# Sheet1.net
KiCad netlist of a schematic drawn in Altium Designer
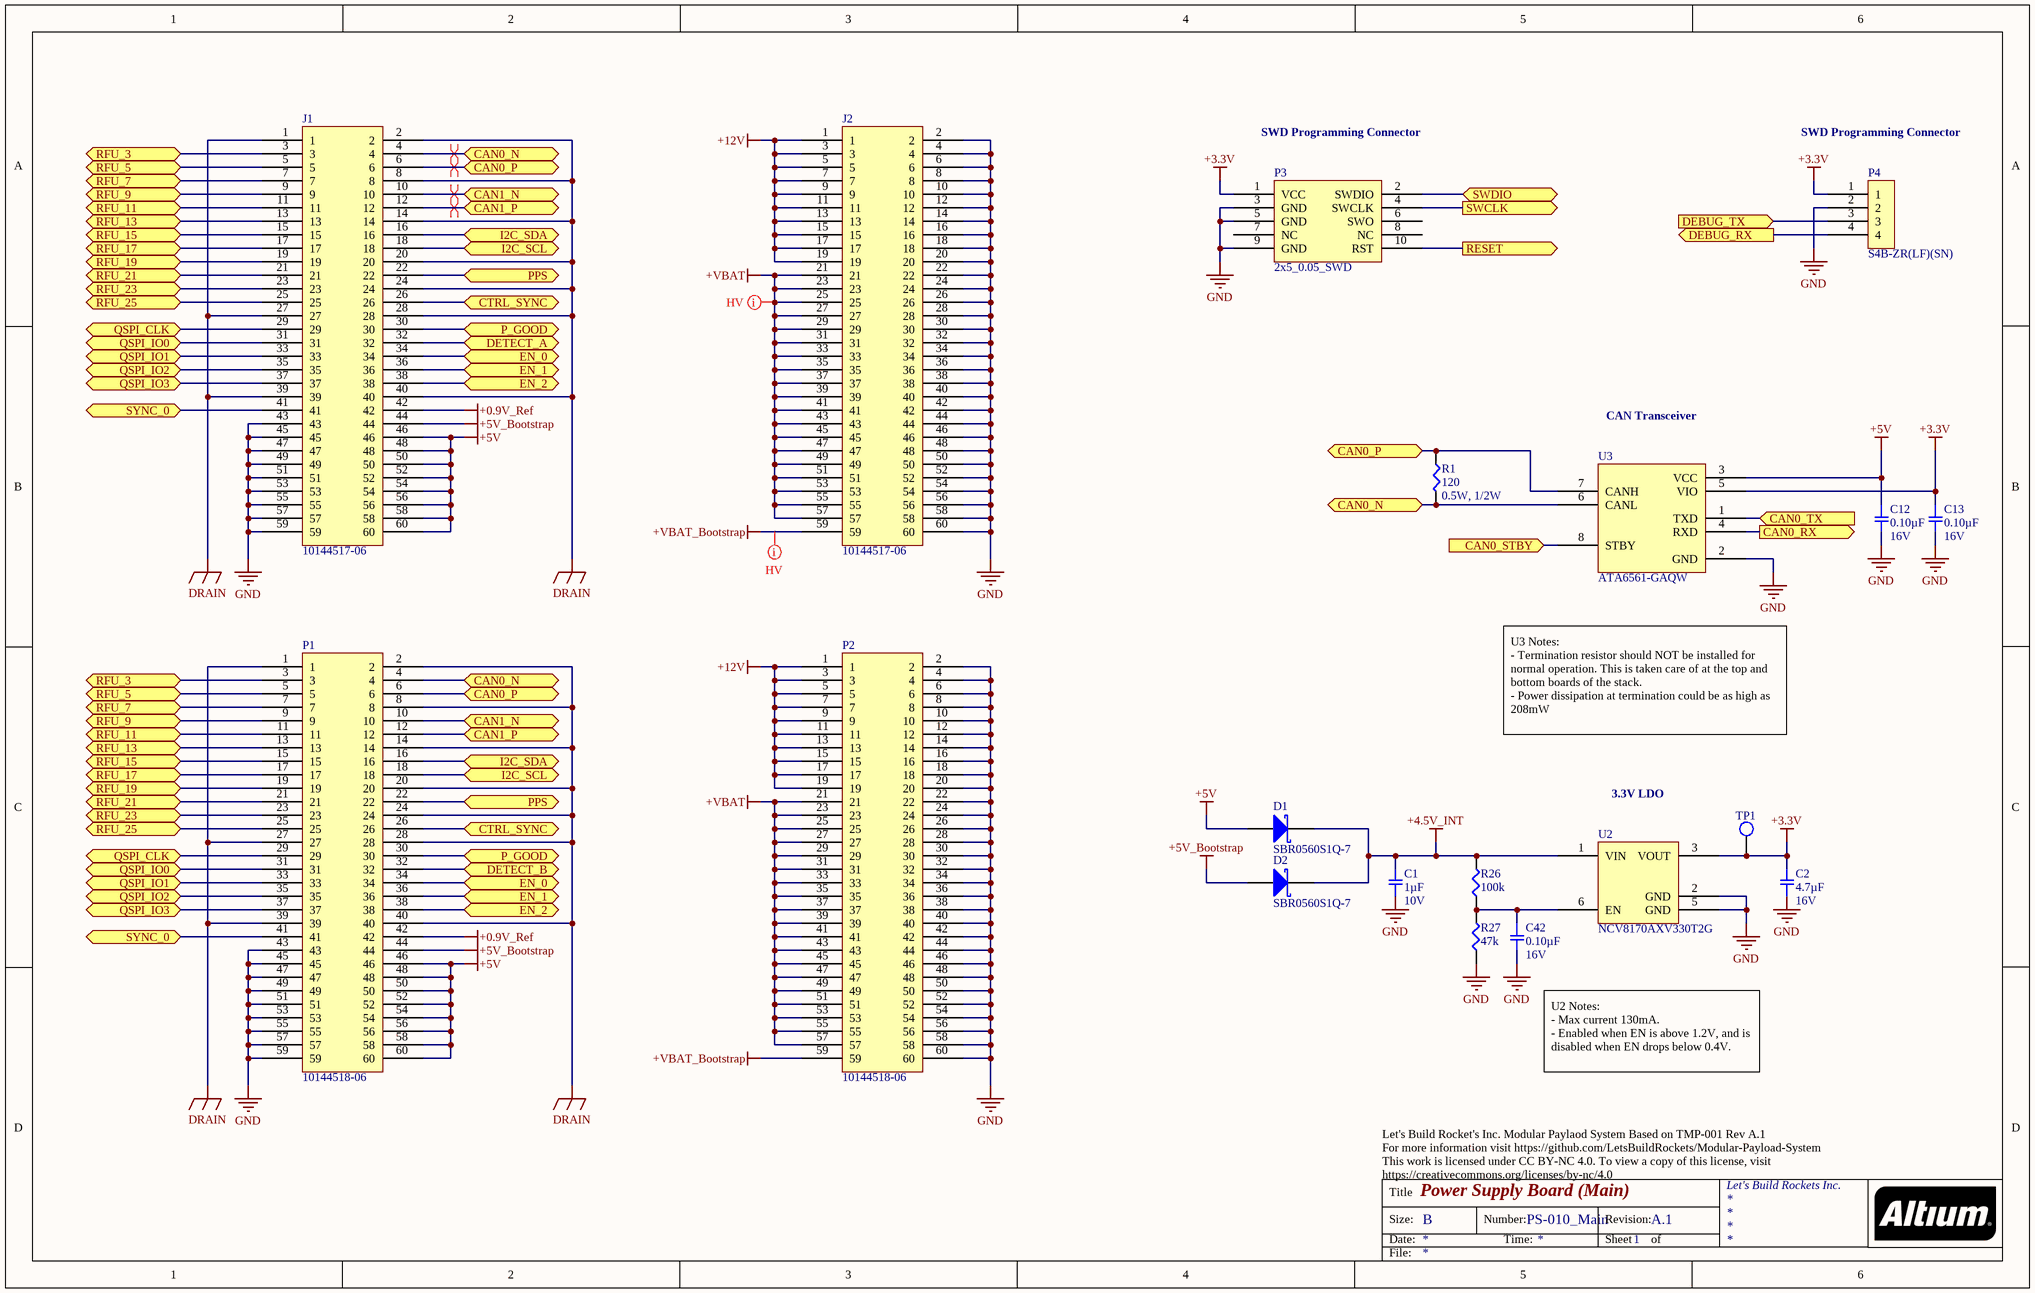
[diagram p0: Sheet1.SchDoc]

(export (version "E")
  (design (tool "Eeschema 10.0.6"))
  (components
    (comp (ref "C1")
      (value "1µF")
      (footprint "SMD-0402C")
      (description "CAP CER 1UF 10V X7S 0402")
      (fields
        (field (name "DIGI-KEY PART NUMBER") "490-13409-1-ND")
        (field (name "PART NUMBER") "GCM155C71A105KE38D")
        (field (name "VOLTAGE") "10V")
      )
      (libsource (lib "capacitor_murata_0402") (part "GCM155C71A105KE38D"))
    )
    (comp (ref "C2")
      (value "4.7µF")
      (footprint "SMD-0805C")
      (description "CAP CER 4.7UF 16V X7R 0805")
      (fields
        (field (name "DIGI-KEY PART NUMBER") "490-10557-1-ND")
        (field (name "PART NUMBER") "GCJ21BR71C475KA01L")
        (field (name "VOLTAGE") "16V")
      )
      (libsource (lib "capacitor_murata_0805") (part "GCJ21BR71C475KA01L"))
    )
    (comp (ref "C12")
      (value "0.10µF")
      (footprint "SMD-0402C")
      (description "CAP CER 0.1UF 16V X7R 0402")
      (fields
        (field (name "DIGI-KEY PART NUMBER") "490-4759-1-ND")
        (field (name "PART NUMBER") "GCM155R71C104KA55D")
        (field (name "VOLTAGE") "16V")
      )
      (libsource (lib "capacitor_murata_0402") (part "GCM155R71C104KA55D"))
    )
    (comp (ref "C13")
      (value "0.10µF")
      (footprint "SMD-0402C")
      (description "CAP CER 0.1UF 16V X7R 0402")
      (fields
        (field (name "DIGI-KEY PART NUMBER") "490-4759-1-ND")
        (field (name "PART NUMBER") "GCM155R71C104KA55D")
        (field (name "VOLTAGE") "16V")
      )
      (libsource (lib "capacitor_murata_0402") (part "GCM155R71C104KA55D"))
    )
    (comp (ref "C42")
      (value "0.10µF")
      (footprint "SMD-0402C")
      (description "CAP CER 0.1UF 16V X7R 0402")
      (fields
        (field (name "DIGI-KEY PART NUMBER") "490-4759-1-ND")
        (field (name "PART NUMBER") "GCM155R71C104KA55D")
        (field (name "VOLTAGE") "16V")
      )
      (libsource (lib "capacitor_murata_0402") (part "GCM155R71C104KA55D"))
    )
    (comp (ref "D1")
      (value "SBR0560S1Q-7")
      (footprint "SOD123")
      (libsource (lib "ModularPayload") (part "SBR0560S1Q-7"))
    )
    (comp (ref "D2")
      (value "SBR0560S1Q-7")
      (footprint "SOD123")
      (libsource (lib "ModularPayload") (part "SBR0560S1Q-7"))
    )
    (comp (ref "J1")
      (value "10144517-06")
      (footprint "10144517-062802LF")
      (libsource (lib "ModularPayload") (part "10144517-06"))
    )
    (comp (ref "J2")
      (value "10144517-06")
      (footprint "10144517-062802LF")
      (libsource (lib "ModularPayload") (part "10144517-06"))
    )
    (comp (ref "P1")
      (value "10144518-06")
      (footprint "10144518-064802LF")
      (libsource (lib "ModularPayload") (part "10144518-06"))
    )
    (comp (ref "P2")
      (value "10144518-06")
      (footprint "10144518-064802LF")
      (libsource (lib "ModularPayload") (part "10144518-06"))
    )
    (comp (ref "P3")
      (value "2x5_0.05_SWD")
      (footprint "2x5_0.05_R")
      (libsource (lib "ModularPayload") (part "2x5_0.05_SWD"))
    )
    (comp (ref "P4")
      (value "S4B-ZR(LF)(SN)")
      (footprint "S4B-ZR(LF)(SN)")
      (libsource (lib "ModularPayload") (part "S4B-ZR(LF)(SN)"))
    )
    (comp (ref "R1")
      (value "120")
      (footprint "SMD-0805-RES")
      (description "RES SMD 120 OHM 5% 1/2W 0805")
      (fields
        (field (name "PART NUMBER") "ERJ-P6WJ121V")
        (field (name "DIGI-KEY PART NUMBER") "P16943CT-ND")
        (field (name "POWER (WATTS)") "0.5W, 1/2W")
      )
      (libsource (lib "Panasonic_ERJ_0805") (part "ERJ-P6WJ121V"))
    )
    (comp (ref "R26")
      (value "100k")
      (footprint "SMD-0402-RES")
      (description "RES SMD 100K OHM 5% 1/10W 0402")
      (fields (field (name "PART NUMBER") "ERJ-2GEJ104X") (field (name "DIGI-KEY PART NUMBER") "P100KJCT-ND"))
      (libsource (lib "Panasonic_ERJ_0402") (part "ERJ-2GEJ104X"))
    )
    (comp (ref "R27")
      (value "47k")
      (footprint "SMD-0402-RES")
      (description "RES SMD 47K OHM 5% 1/10W 0402")
      (fields (field (name "PART NUMBER") "ERJ-2GEJ473X") (field (name "DIGI-KEY PART NUMBER") "P47KJCT-ND"))
      (libsource (lib "Panasonic_ERJ_0402") (part "ERJ-2GEJ473X"))
    )
    (comp (ref "TP1") (value "TP") (footprint "TP_SMD_40") (libsource (lib "TP") (part "TP")))
    (comp (ref "U2")
      (value "NCV8170AXV330T2G")
      (footprint "SOTFL50P160X60-6N")
      (libsource (lib "ModularPayload") (part "NCV8170AXV330T2G"))
    )
    (comp (ref "U3")
      (value "ATA6561-GAQW")
      (footprint "SOIC127P600X175-8N")
      (libsource (lib "ModularPayload") (part "ATA6561-GAQW"))
    )
  )
  (nets
    (net (code "1") (name "+0.9V_Ref") (class "Default")
      (node (ref "J1") (pin "42") (pinfunction "42_42") (pintype "passive"))
      (node (ref "P1") (pin "42") (pinfunction "42_42") (pintype "passive"))
    )
    (net (code "2") (name "+3.3V") (class "Default")
      (node (ref "C13") (pin "1") (pinfunction "1_1") (pintype "passive"))
      (node (ref "C2") (pin "2") (pinfunction "2_2") (pintype "passive"))
      (node (ref "P3") (pin "1") (pinfunction "VCC_1") (pintype "passive"))
      (node (ref "P4") (pin "1") (pinfunction "1_1") (pintype "passive"))
      (node (ref "TP1") (pin "1") (pintype "passive"))
      (node (ref "U2") (pin "3") (pinfunction "VOUT_3") (pintype "passive"))
      (node (ref "U3") (pin "5") (pinfunction "VIO_5") (pintype "passive"))
    )
    (net (code "3") (name "+4.5V_INT") (class "Default")
      (node (ref "C1") (pin "2") (pinfunction "2_2") (pintype "passive"))
      (node (ref "D1") (pin "K") (pinfunction "K_K") (pintype "passive"))
      (node (ref "D2") (pin "K") (pinfunction "K_K") (pintype "passive"))
      (node (ref "R26") (pin "2") (pinfunction "2_2") (pintype "passive"))
      (node (ref "U2") (pin "1") (pinfunction "VIN_1") (pintype "passive"))
    )
    (net (code "4") (name "+5V") (class "Default")
      (node (ref "C12") (pin "1") (pinfunction "1_1") (pintype "passive"))
      (node (ref "D1") (pin "A") (pinfunction "A_A") (pintype "passive"))
      (node (ref "J1") (pin "46") (pinfunction "46_46") (pintype "passive"))
      (node (ref "J1") (pin "48") (pinfunction "48_48") (pintype "passive"))
      (node (ref "J1") (pin "50") (pinfunction "50_50") (pintype "passive"))
      (node (ref "J1") (pin "52") (pinfunction "52_52") (pintype "passive"))
      (node (ref "J1") (pin "54") (pinfunction "54_54") (pintype "passive"))
      (node (ref "J1") (pin "56") (pinfunction "56_56") (pintype "passive"))
      (node (ref "J1") (pin "58") (pinfunction "58_58") (pintype "passive"))
      (node (ref "J1") (pin "60") (pinfunction "60_60") (pintype "passive"))
      (node (ref "P1") (pin "46") (pinfunction "46_46") (pintype "passive"))
      (node (ref "P1") (pin "48") (pinfunction "48_48") (pintype "passive"))
      (node (ref "P1") (pin "50") (pinfunction "50_50") (pintype "passive"))
      (node (ref "P1") (pin "52") (pinfunction "52_52") (pintype "passive"))
      (node (ref "P1") (pin "54") (pinfunction "54_54") (pintype "passive"))
      (node (ref "P1") (pin "56") (pinfunction "56_56") (pintype "passive"))
      (node (ref "P1") (pin "58") (pinfunction "58_58") (pintype "passive"))
      (node (ref "P1") (pin "60") (pinfunction "60_60") (pintype "passive"))
      (node (ref "U3") (pin "3") (pinfunction "VCC_3") (pintype "passive"))
    )
    (net (code "5") (name "+5V_Bootstrap") (class "Default")
      (node (ref "D2") (pin "A") (pinfunction "A_A") (pintype "passive"))
      (node (ref "J1") (pin "44") (pinfunction "44_44") (pintype "passive"))
      (node (ref "P1") (pin "44") (pinfunction "44_44") (pintype "passive"))
    )
    (net (code "6") (name "+12V") (class "Default")
      (node (ref "J2") (pin "1") (pinfunction "1_1") (pintype "passive"))
      (node (ref "J2") (pin "11") (pinfunction "11_11") (pintype "passive"))
      (node (ref "J2") (pin "13") (pinfunction "13_13") (pintype "passive"))
      (node (ref "J2") (pin "15") (pinfunction "15_15") (pintype "passive"))
      (node (ref "J2") (pin "17") (pinfunction "17_17") (pintype "passive"))
      (node (ref "J2") (pin "19") (pinfunction "19_19") (pintype "passive"))
      (node (ref "J2") (pin "3") (pinfunction "3_3") (pintype "passive"))
      (node (ref "J2") (pin "5") (pinfunction "5_5") (pintype "passive"))
      (node (ref "J2") (pin "7") (pinfunction "7_7") (pintype "passive"))
      (node (ref "J2") (pin "9") (pinfunction "9_9") (pintype "passive"))
      (node (ref "P2") (pin "1") (pinfunction "1_1") (pintype "passive"))
      (node (ref "P2") (pin "11") (pinfunction "11_11") (pintype "passive"))
      (node (ref "P2") (pin "13") (pinfunction "13_13") (pintype "passive"))
      (node (ref "P2") (pin "15") (pinfunction "15_15") (pintype "passive"))
      (node (ref "P2") (pin "17") (pinfunction "17_17") (pintype "passive"))
      (node (ref "P2") (pin "19") (pinfunction "19_19") (pintype "passive"))
      (node (ref "P2") (pin "3") (pinfunction "3_3") (pintype "passive"))
      (node (ref "P2") (pin "5") (pinfunction "5_5") (pintype "passive"))
      (node (ref "P2") (pin "7") (pinfunction "7_7") (pintype "passive"))
      (node (ref "P2") (pin "9") (pinfunction "9_9") (pintype "passive"))
    )
    (net (code "7") (name "+VBAT") (class "Default")
      (node (ref "J2") (pin "21") (pinfunction "21_21") (pintype "passive"))
      (node (ref "J2") (pin "23") (pinfunction "23_23") (pintype "passive"))
      (node (ref "J2") (pin "25") (pinfunction "25_25") (pintype "passive"))
      (node (ref "J2") (pin "27") (pinfunction "27_27") (pintype "passive"))
      (node (ref "J2") (pin "29") (pinfunction "29_29") (pintype "passive"))
      (node (ref "J2") (pin "31") (pinfunction "31_31") (pintype "passive"))
      (node (ref "J2") (pin "33") (pinfunction "33_33") (pintype "passive"))
      (node (ref "J2") (pin "35") (pinfunction "35_35") (pintype "passive"))
      (node (ref "J2") (pin "37") (pinfunction "37_37") (pintype "passive"))
      (node (ref "J2") (pin "39") (pinfunction "39_39") (pintype "passive"))
      (node (ref "J2") (pin "41") (pinfunction "41_41") (pintype "passive"))
      (node (ref "J2") (pin "43") (pinfunction "43_43") (pintype "passive"))
      (node (ref "J2") (pin "45") (pinfunction "45_45") (pintype "passive"))
      (node (ref "J2") (pin "47") (pinfunction "47_47") (pintype "passive"))
      (node (ref "J2") (pin "49") (pinfunction "49_49") (pintype "passive"))
      (node (ref "J2") (pin "51") (pinfunction "51_51") (pintype "passive"))
      (node (ref "J2") (pin "53") (pinfunction "53_53") (pintype "passive"))
      (node (ref "J2") (pin "55") (pinfunction "55_55") (pintype "passive"))
      (node (ref "J2") (pin "57") (pinfunction "57_57") (pintype "passive"))
      (node (ref "P2") (pin "21") (pinfunction "21_21") (pintype "passive"))
      (node (ref "P2") (pin "23") (pinfunction "23_23") (pintype "passive"))
      (node (ref "P2") (pin "25") (pinfunction "25_25") (pintype "passive"))
      (node (ref "P2") (pin "27") (pinfunction "27_27") (pintype "passive"))
      (node (ref "P2") (pin "29") (pinfunction "29_29") (pintype "passive"))
      (node (ref "P2") (pin "31") (pinfunction "31_31") (pintype "passive"))
      (node (ref "P2") (pin "33") (pinfunction "33_33") (pintype "passive"))
      (node (ref "P2") (pin "35") (pinfunction "35_35") (pintype "passive"))
      (node (ref "P2") (pin "37") (pinfunction "37_37") (pintype "passive"))
      (node (ref "P2") (pin "39") (pinfunction "39_39") (pintype "passive"))
      (node (ref "P2") (pin "41") (pinfunction "41_41") (pintype "passive"))
      (node (ref "P2") (pin "43") (pinfunction "43_43") (pintype "passive"))
      (node (ref "P2") (pin "45") (pinfunction "45_45") (pintype "passive"))
      (node (ref "P2") (pin "47") (pinfunction "47_47") (pintype "passive"))
      (node (ref "P2") (pin "49") (pinfunction "49_49") (pintype "passive"))
      (node (ref "P2") (pin "51") (pinfunction "51_51") (pintype "passive"))
      (node (ref "P2") (pin "53") (pinfunction "53_53") (pintype "passive"))
      (node (ref "P2") (pin "55") (pinfunction "55_55") (pintype "passive"))
      (node (ref "P2") (pin "57") (pinfunction "57_57") (pintype "passive"))
    )
    (net (code "8") (name "+VBAT_Bootstrap") (class "Default")
      (node (ref "J2") (pin "59") (pinfunction "59_59") (pintype "passive"))
      (node (ref "P2") (pin "59") (pinfunction "59_59") (pintype "passive"))
    )
    (net (code "9") (name "/CAN0_N") (class "Default")
      (node (ref "J1") (pin "4") (pinfunction "4_4") (pintype "passive"))
      (node (ref "P1") (pin "4") (pinfunction "4_4") (pintype "passive"))
      (node (ref "R1") (pin "2") (pinfunction "2_2") (pintype "passive"))
      (node (ref "U3") (pin "6") (pinfunction "CANL_6") (pintype "passive"))
    )
    (net (code "10") (name "/CAN0_P") (class "Default")
      (node (ref "J1") (pin "6") (pinfunction "6_6") (pintype "passive"))
      (node (ref "P1") (pin "6") (pinfunction "6_6") (pintype "passive"))
      (node (ref "R1") (pin "1") (pinfunction "1_1") (pintype "passive"))
      (node (ref "U3") (pin "7") (pinfunction "CANH_7") (pintype "passive"))
    )
    (net (code "11") (name "/CAN0_RX") (class "Default")
      (node (ref "U3") (pin "4") (pinfunction "RXD_4") (pintype "passive"))
    )
    (net (code "12") (name "/CAN0_STBY") (class "Default")
      (node (ref "U3") (pin "8") (pinfunction "STBY_8") (pintype "passive"))
    )
    (net (code "13") (name "/CAN0_TX") (class "Default")
      (node (ref "U3") (pin "1") (pinfunction "TXD_1") (pintype "passive"))
    )
    (net (code "14") (name "/CAN1_N") (class "Default")
      (node (ref "J1") (pin "10") (pinfunction "10_10") (pintype "passive"))
      (node (ref "P1") (pin "10") (pinfunction "10_10") (pintype "passive"))
    )
    (net (code "15") (name "/CAN1_P") (class "Default")
      (node (ref "J1") (pin "12") (pinfunction "12_12") (pintype "passive"))
      (node (ref "P1") (pin "12") (pinfunction "12_12") (pintype "passive"))
    )
    (net (code "16") (name "/CTRL_SYNC") (class "Default")
      (node (ref "J1") (pin "26") (pinfunction "26_26") (pintype "passive"))
      (node (ref "P1") (pin "26") (pinfunction "26_26") (pintype "passive"))
    )
    (net (code "17") (name "/DEBUG_RX") (class "Default")
      (node (ref "P4") (pin "4") (pinfunction "4_4") (pintype "passive"))
    )
    (net (code "18") (name "/DEBUG_TX") (class "Default")
      (node (ref "P4") (pin "3") (pinfunction "3_3") (pintype "passive"))
    )
    (net (code "19") (name "/DETECT_A") (class "Default")
      (node (ref "J1") (pin "32") (pinfunction "32_32") (pintype "passive"))
    )
    (net (code "20") (name "/DETECT_B") (class "Default")
      (node (ref "P1") (pin "32") (pinfunction "32_32") (pintype "passive"))
    )
    (net (code "21") (name "/EN_0") (class "Default")
      (node (ref "J1") (pin "34") (pinfunction "34_34") (pintype "passive"))
      (node (ref "P1") (pin "34") (pinfunction "34_34") (pintype "passive"))
    )
    (net (code "22") (name "/EN_1") (class "Default")
      (node (ref "J1") (pin "36") (pinfunction "36_36") (pintype "passive"))
      (node (ref "P1") (pin "36") (pinfunction "36_36") (pintype "passive"))
    )
    (net (code "23") (name "/EN_2") (class "Default")
      (node (ref "J1") (pin "38") (pinfunction "38_38") (pintype "passive"))
      (node (ref "P1") (pin "38") (pinfunction "38_38") (pintype "passive"))
    )
    (net (code "24") (name "/I2C_SCL") (class "Default")
      (node (ref "J1") (pin "18") (pinfunction "18_18") (pintype "passive"))
      (node (ref "P1") (pin "18") (pinfunction "18_18") (pintype "passive"))
    )
    (net (code "25") (name "/I2C_SDA") (class "Default")
      (node (ref "J1") (pin "16") (pinfunction "16_16") (pintype "passive"))
      (node (ref "P1") (pin "16") (pinfunction "16_16") (pintype "passive"))
    )
    (net (code "26") (name "/PPS") (class "Default")
      (node (ref "J1") (pin "22") (pinfunction "22_22") (pintype "passive"))
      (node (ref "P1") (pin "22") (pinfunction "22_22") (pintype "passive"))
    )
    (net (code "27") (name "/P_GOOD") (class "Default")
      (node (ref "J1") (pin "30") (pinfunction "30_30") (pintype "passive"))
      (node (ref "P1") (pin "30") (pinfunction "30_30") (pintype "passive"))
    )
    (net (code "28") (name "/QSPI_CLK") (class "Default")
      (node (ref "J1") (pin "29") (pinfunction "29_29") (pintype "passive"))
      (node (ref "P1") (pin "29") (pinfunction "29_29") (pintype "passive"))
    )
    (net (code "29") (name "/QSPI_IO0") (class "Default")
      (node (ref "J1") (pin "31") (pinfunction "31_31") (pintype "passive"))
      (node (ref "P1") (pin "31") (pinfunction "31_31") (pintype "passive"))
    )
    (net (code "30") (name "/QSPI_IO1") (class "Default")
      (node (ref "J1") (pin "33") (pinfunction "33_33") (pintype "passive"))
      (node (ref "P1") (pin "33") (pinfunction "33_33") (pintype "passive"))
    )
    (net (code "31") (name "/QSPI_IO2") (class "Default")
      (node (ref "J1") (pin "35") (pinfunction "35_35") (pintype "passive"))
      (node (ref "P1") (pin "35") (pinfunction "35_35") (pintype "passive"))
    )
    (net (code "32") (name "/QSPI_IO3") (class "Default")
      (node (ref "J1") (pin "37") (pinfunction "37_37") (pintype "passive"))
      (node (ref "P1") (pin "37") (pinfunction "37_37") (pintype "passive"))
    )
    (net (code "33") (name "/RESET") (class "Default")
      (node (ref "P3") (pin "10") (pinfunction "RST_10") (pintype "passive"))
    )
    (net (code "34") (name "/RFU_3") (class "Default")
      (node (ref "J1") (pin "3") (pinfunction "3_3") (pintype "passive"))
      (node (ref "P1") (pin "3") (pinfunction "3_3") (pintype "passive"))
    )
    (net (code "35") (name "/RFU_5") (class "Default")
      (node (ref "J1") (pin "5") (pinfunction "5_5") (pintype "passive"))
      (node (ref "P1") (pin "5") (pinfunction "5_5") (pintype "passive"))
    )
    (net (code "36") (name "/RFU_7") (class "Default")
      (node (ref "J1") (pin "7") (pinfunction "7_7") (pintype "passive"))
      (node (ref "P1") (pin "7") (pinfunction "7_7") (pintype "passive"))
    )
    (net (code "37") (name "/RFU_9") (class "Default")
      (node (ref "J1") (pin "9") (pinfunction "9_9") (pintype "passive"))
      (node (ref "P1") (pin "9") (pinfunction "9_9") (pintype "passive"))
    )
    (net (code "38") (name "/RFU_11") (class "Default")
      (node (ref "J1") (pin "11") (pinfunction "11_11") (pintype "passive"))
      (node (ref "P1") (pin "11") (pinfunction "11_11") (pintype "passive"))
    )
    (net (code "39") (name "/RFU_13") (class "Default")
      (node (ref "J1") (pin "13") (pinfunction "13_13") (pintype "passive"))
      (node (ref "P1") (pin "13") (pinfunction "13_13") (pintype "passive"))
    )
    (net (code "40") (name "/RFU_15") (class "Default")
      (node (ref "J1") (pin "15") (pinfunction "15_15") (pintype "passive"))
      (node (ref "P1") (pin "15") (pinfunction "15_15") (pintype "passive"))
    )
    (net (code "41") (name "/RFU_17") (class "Default")
      (node (ref "J1") (pin "17") (pinfunction "17_17") (pintype "passive"))
      (node (ref "P1") (pin "17") (pinfunction "17_17") (pintype "passive"))
    )
    (net (code "42") (name "/RFU_19") (class "Default")
      (node (ref "J1") (pin "19") (pinfunction "19_19") (pintype "passive"))
      (node (ref "P1") (pin "19") (pinfunction "19_19") (pintype "passive"))
    )
    (net (code "43") (name "/RFU_21") (class "Default")
      (node (ref "J1") (pin "21") (pinfunction "21_21") (pintype "passive"))
      (node (ref "P1") (pin "21") (pinfunction "21_21") (pintype "passive"))
    )
    (net (code "44") (name "/RFU_23") (class "Default")
      (node (ref "J1") (pin "23") (pinfunction "23_23") (pintype "passive"))
      (node (ref "P1") (pin "23") (pinfunction "23_23") (pintype "passive"))
    )
    (net (code "45") (name "/RFU_25") (class "Default")
      (node (ref "J1") (pin "25") (pinfunction "25_25") (pintype "passive"))
      (node (ref "P1") (pin "25") (pinfunction "25_25") (pintype "passive"))
    )
    (net (code "46") (name "/SWCLK") (class "Default")
      (node (ref "P3") (pin "4") (pinfunction "SWCLK_4") (pintype "passive"))
    )
    (net (code "47") (name "/SWDIO") (class "Default")
      (node (ref "P3") (pin "2") (pinfunction "SWDIO_2") (pintype "passive"))
    )
    (net (code "48") (name "/SYNC_0") (class "Default")
      (node (ref "J1") (pin "41") (pinfunction "41_41") (pintype "passive"))
      (node (ref "P1") (pin "41") (pinfunction "41_41") (pintype "passive"))
    )
    (net (code "49") (name "DRAIN") (class "Default")
      (node (ref "J1") (pin "1") (pinfunction "1_1") (pintype "passive"))
      (node (ref "J1") (pin "14") (pinfunction "14_14") (pintype "passive"))
      (node (ref "J1") (pin "2") (pinfunction "2_2") (pintype "passive"))
      (node (ref "J1") (pin "20") (pinfunction "20_20") (pintype "passive"))
      (node (ref "J1") (pin "24") (pinfunction "24_24") (pintype "passive"))
      (node (ref "J1") (pin "27") (pinfunction "27_27") (pintype "passive"))
      (node (ref "J1") (pin "28") (pinfunction "28_28") (pintype "passive"))
      (node (ref "J1") (pin "39") (pinfunction "39_39") (pintype "passive"))
      (node (ref "J1") (pin "40") (pinfunction "40_40") (pintype "passive"))
      (node (ref "J1") (pin "8") (pinfunction "8_8") (pintype "passive"))
      (node (ref "P1") (pin "1") (pinfunction "1_1") (pintype "passive"))
      (node (ref "P1") (pin "14") (pinfunction "14_14") (pintype "passive"))
      (node (ref "P1") (pin "2") (pinfunction "2_2") (pintype "passive"))
      (node (ref "P1") (pin "20") (pinfunction "20_20") (pintype "passive"))
      (node (ref "P1") (pin "24") (pinfunction "24_24") (pintype "passive"))
      (node (ref "P1") (pin "27") (pinfunction "27_27") (pintype "passive"))
      (node (ref "P1") (pin "28") (pinfunction "28_28") (pintype "passive"))
      (node (ref "P1") (pin "39") (pinfunction "39_39") (pintype "passive"))
      (node (ref "P1") (pin "40") (pinfunction "40_40") (pintype "passive"))
      (node (ref "P1") (pin "8") (pinfunction "8_8") (pintype "passive"))
    )
    (net (code "50") (name "GND") (class "Default")
      (node (ref "C1") (pin "1") (pinfunction "1_1") (pintype "passive"))
      (node (ref "C12") (pin "2") (pinfunction "2_2") (pintype "passive"))
      (node (ref "C13") (pin "2") (pinfunction "2_2") (pintype "passive"))
      (node (ref "C2") (pin "1") (pinfunction "1_1") (pintype "passive"))
      (node (ref "C42") (pin "2") (pinfunction "2_2") (pintype "passive"))
      (node (ref "J1") (pin "43") (pinfunction "43_43") (pintype "passive"))
      (node (ref "J1") (pin "45") (pinfunction "45_45") (pintype "passive"))
      (node (ref "J1") (pin "47") (pinfunction "47_47") (pintype "passive"))
      (node (ref "J1") (pin "49") (pinfunction "49_49") (pintype "passive"))
      (node (ref "J1") (pin "51") (pinfunction "51_51") (pintype "passive"))
      (node (ref "J1") (pin "53") (pinfunction "53_53") (pintype "passive"))
      (node (ref "J1") (pin "55") (pinfunction "55_55") (pintype "passive"))
      (node (ref "J1") (pin "57") (pinfunction "57_57") (pintype "passive"))
      (node (ref "J1") (pin "59") (pinfunction "59_59") (pintype "passive"))
      (node (ref "J2") (pin "10") (pinfunction "10_10") (pintype "passive"))
      (node (ref "J2") (pin "12") (pinfunction "12_12") (pintype "passive"))
      (node (ref "J2") (pin "14") (pinfunction "14_14") (pintype "passive"))
      (node (ref "J2") (pin "16") (pinfunction "16_16") (pintype "passive"))
      (node (ref "J2") (pin "18") (pinfunction "18_18") (pintype "passive"))
      (node (ref "J2") (pin "2") (pinfunction "2_2") (pintype "passive"))
      (node (ref "J2") (pin "20") (pinfunction "20_20") (pintype "passive"))
      (node (ref "J2") (pin "22") (pinfunction "22_22") (pintype "passive"))
      (node (ref "J2") (pin "24") (pinfunction "24_24") (pintype "passive"))
      (node (ref "J2") (pin "26") (pinfunction "26_26") (pintype "passive"))
      (node (ref "J2") (pin "28") (pinfunction "28_28") (pintype "passive"))
      (node (ref "J2") (pin "30") (pinfunction "30_30") (pintype "passive"))
      (node (ref "J2") (pin "32") (pinfunction "32_32") (pintype "passive"))
      (node (ref "J2") (pin "34") (pinfunction "34_34") (pintype "passive"))
      (node (ref "J2") (pin "36") (pinfunction "36_36") (pintype "passive"))
      (node (ref "J2") (pin "38") (pinfunction "38_38") (pintype "passive"))
      (node (ref "J2") (pin "4") (pinfunction "4_4") (pintype "passive"))
      (node (ref "J2") (pin "40") (pinfunction "40_40") (pintype "passive"))
      (node (ref "J2") (pin "42") (pinfunction "42_42") (pintype "passive"))
      (node (ref "J2") (pin "44") (pinfunction "44_44") (pintype "passive"))
      (node (ref "J2") (pin "46") (pinfunction "46_46") (pintype "passive"))
      (node (ref "J2") (pin "48") (pinfunction "48_48") (pintype "passive"))
      (node (ref "J2") (pin "50") (pinfunction "50_50") (pintype "passive"))
      (node (ref "J2") (pin "52") (pinfunction "52_52") (pintype "passive"))
      (node (ref "J2") (pin "54") (pinfunction "54_54") (pintype "passive"))
      (node (ref "J2") (pin "56") (pinfunction "56_56") (pintype "passive"))
      (node (ref "J2") (pin "58") (pinfunction "58_58") (pintype "passive"))
      (node (ref "J2") (pin "6") (pinfunction "6_6") (pintype "passive"))
      (node (ref "J2") (pin "60") (pinfunction "60_60") (pintype "passive"))
      (node (ref "J2") (pin "8") (pinfunction "8_8") (pintype "passive"))
      (node (ref "P1") (pin "43") (pinfunction "43_43") (pintype "passive"))
      (node (ref "P1") (pin "45") (pinfunction "45_45") (pintype "passive"))
      (node (ref "P1") (pin "47") (pinfunction "47_47") (pintype "passive"))
      (node (ref "P1") (pin "49") (pinfunction "49_49") (pintype "passive"))
      (node (ref "P1") (pin "51") (pinfunction "51_51") (pintype "passive"))
      (node (ref "P1") (pin "53") (pinfunction "53_53") (pintype "passive"))
      (node (ref "P1") (pin "55") (pinfunction "55_55") (pintype "passive"))
      (node (ref "P1") (pin "57") (pinfunction "57_57") (pintype "passive"))
      (node (ref "P1") (pin "59") (pinfunction "59_59") (pintype "passive"))
      (node (ref "P2") (pin "10") (pinfunction "10_10") (pintype "passive"))
      (node (ref "P2") (pin "12") (pinfunction "12_12") (pintype "passive"))
      (node (ref "P2") (pin "14") (pinfunction "14_14") (pintype "passive"))
      (node (ref "P2") (pin "16") (pinfunction "16_16") (pintype "passive"))
      (node (ref "P2") (pin "18") (pinfunction "18_18") (pintype "passive"))
      (node (ref "P2") (pin "2") (pinfunction "2_2") (pintype "passive"))
      (node (ref "P2") (pin "20") (pinfunction "20_20") (pintype "passive"))
      (node (ref "P2") (pin "22") (pinfunction "22_22") (pintype "passive"))
      (node (ref "P2") (pin "24") (pinfunction "24_24") (pintype "passive"))
      (node (ref "P2") (pin "26") (pinfunction "26_26") (pintype "passive"))
      (node (ref "P2") (pin "28") (pinfunction "28_28") (pintype "passive"))
      (node (ref "P2") (pin "30") (pinfunction "30_30") (pintype "passive"))
      (node (ref "P2") (pin "32") (pinfunction "32_32") (pintype "passive"))
      (node (ref "P2") (pin "34") (pinfunction "34_34") (pintype "passive"))
      (node (ref "P2") (pin "36") (pinfunction "36_36") (pintype "passive"))
      (node (ref "P2") (pin "38") (pinfunction "38_38") (pintype "passive"))
      (node (ref "P2") (pin "4") (pinfunction "4_4") (pintype "passive"))
      (node (ref "P2") (pin "40") (pinfunction "40_40") (pintype "passive"))
      (node (ref "P2") (pin "42") (pinfunction "42_42") (pintype "passive"))
      (node (ref "P2") (pin "44") (pinfunction "44_44") (pintype "passive"))
      (node (ref "P2") (pin "46") (pinfunction "46_46") (pintype "passive"))
      (node (ref "P2") (pin "48") (pinfunction "48_48") (pintype "passive"))
      (node (ref "P2") (pin "50") (pinfunction "50_50") (pintype "passive"))
      (node (ref "P2") (pin "52") (pinfunction "52_52") (pintype "passive"))
      (node (ref "P2") (pin "54") (pinfunction "54_54") (pintype "passive"))
      (node (ref "P2") (pin "56") (pinfunction "56_56") (pintype "passive"))
      (node (ref "P2") (pin "58") (pinfunction "58_58") (pintype "passive"))
      (node (ref "P2") (pin "6") (pinfunction "6_6") (pintype "passive"))
      (node (ref "P2") (pin "60") (pinfunction "60_60") (pintype "passive"))
      (node (ref "P2") (pin "8") (pinfunction "8_8") (pintype "passive"))
      (node (ref "P3") (pin "3") (pinfunction "GND_3") (pintype "passive"))
      (node (ref "P3") (pin "5") (pinfunction "GND_5") (pintype "passive"))
      (node (ref "P3") (pin "9") (pinfunction "GND_9") (pintype "passive"))
      (node (ref "P4") (pin "2") (pinfunction "2_2") (pintype "passive"))
      (node (ref "R27") (pin "1") (pinfunction "1_1") (pintype "passive"))
      (node (ref "U2") (pin "2") (pinfunction "GND_2") (pintype "passive"))
      (node (ref "U2") (pin "5") (pinfunction "GND_5") (pintype "passive"))
      (node (ref "U3") (pin "2") (pinfunction "GND_2") (pintype "passive"))
    )
    (net (code "51") (name "Net-(U2-EN)") (class "Default")
      (node (ref "C42") (pin "1") (pinfunction "1_1") (pintype "passive"))
      (node (ref "R26") (pin "1") (pinfunction "1_1") (pintype "passive"))
      (node (ref "R27") (pin "2") (pinfunction "2_2") (pintype "passive"))
      (node (ref "U2") (pin "6") (pinfunction "EN_6") (pintype "passive"))
    )
    (net (code "52") (name "unconnected-(P3-NC-Pad7)") (class "Default")
      (node (ref "P3") (pin "7") (pinfunction "NC_7") (pintype "passive"))
    )
    (net (code "53") (name "unconnected-(P3-NC-Pad8)") (class "Default")
      (node (ref "P3") (pin "8") (pinfunction "NC_8") (pintype "passive"))
    )
    (net (code "54") (name "unconnected-(P3-SWO-Pad6)") (class "Default")
      (node (ref "P3") (pin "6") (pinfunction "SWO_6") (pintype "passive"))
    )
  )
)
